# stepper-schematic.net
KiCad netlist of a schematic drawn in Altium Designer
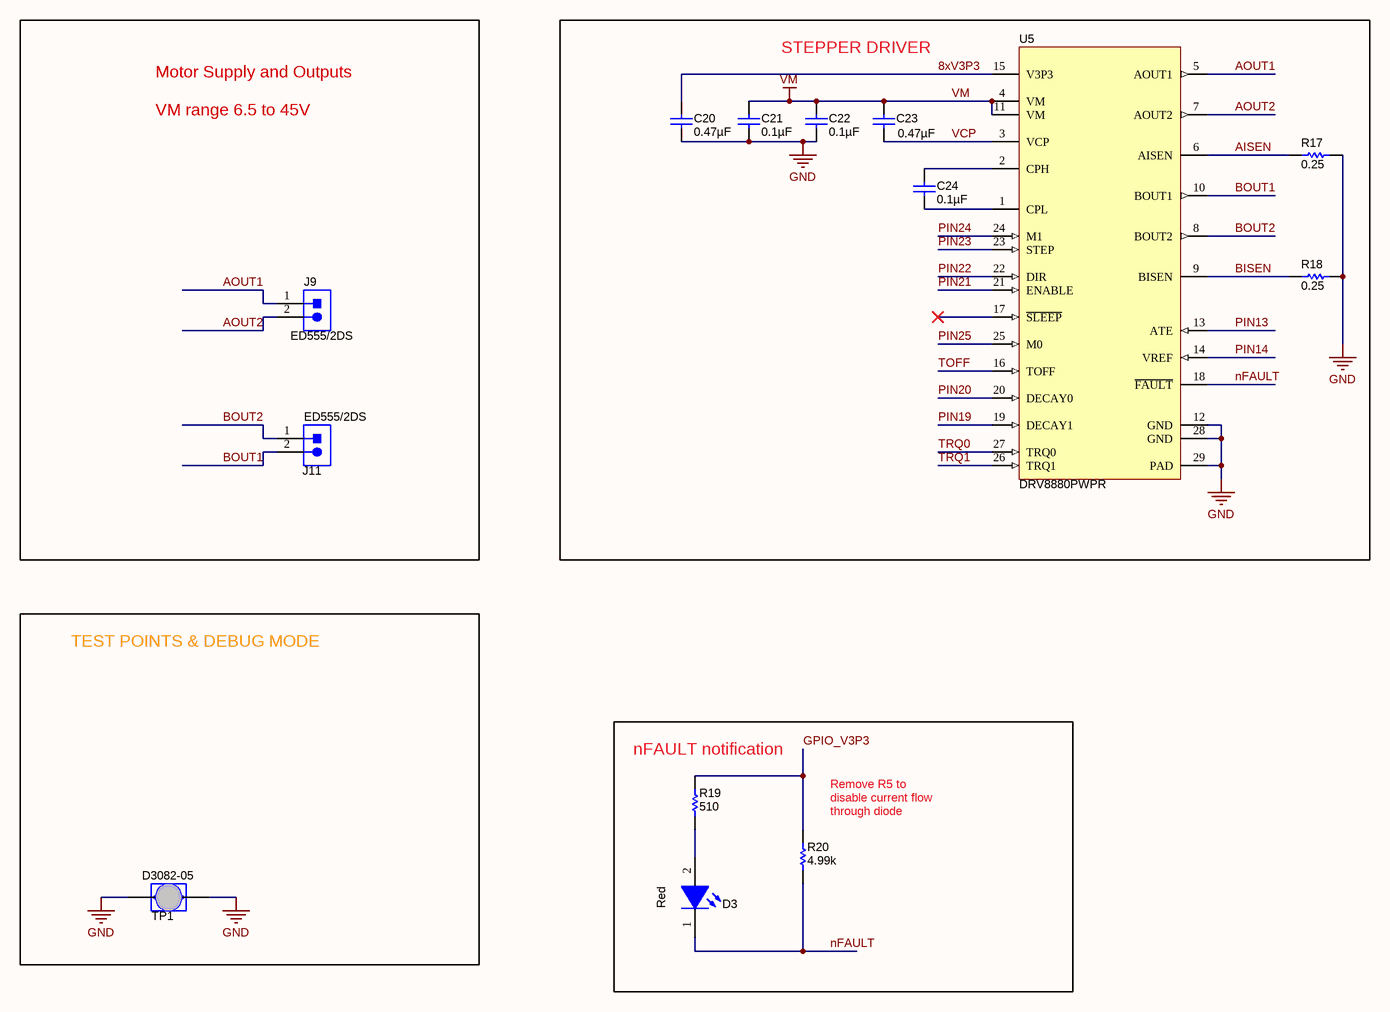
[diagram p0: stepper-schematic.SchDoc]

(export (version "E")
  (design (tool "Eeschema 10.0.6"))
  (components
    (comp (ref "C20")
      (value "C0603C474K9RACTU")
      (footprint "0603L")
      (description "CAP, CERM, 0.47 µF, 6.3 V, +/- 10%, X7R, 0603")
      (fields
        (field (name "MANUFACTURER") "Kemet")
        (field (name "VALUEDISPLAYED") "0.47µF")
        (field (name "PUBLISHER") "Texas Instruments")
      )
      (libsource (lib "drvs-motor") (part "C0603C474K9RACTU"))
    )
    (comp (ref "C21")
      (value "C0805C104K1RACTU")
      (footprint "0805L")
      (description "CAP, CERM, 0.1 µF, 100 V, +/- 10%, X7R, 0805")
      (fields
        (field (name "MANUFACTURER") "Kemet")
        (field (name "VALUEDISPLAYED") "0.1µF")
        (field (name "PUBLISHER") "Texas Instruments")
      )
      (libsource (lib "drvs-motor") (part "C0805C104K1RACTU"))
    )
    (comp (ref "C22")
      (value "C0805C104K1RACTU")
      (footprint "0805L")
      (description "CAP, CERM, 0.1 µF, 100 V, +/- 10%, X7R, 0805")
      (fields
        (field (name "MANUFACTURER") "Kemet")
        (field (name "VALUEDISPLAYED") "0.1µF")
        (field (name "PUBLISHER") "Texas Instruments")
      )
      (libsource (lib "drvs-motor") (part "C0805C104K1RACTU"))
    )
    (comp (ref "C23")
      (value "C2012X7R1E474K")
      (footprint "0805L")
      (description "CAP, CERM, 0.47 µF, 25 V, +/- 10%, X7R, 0805")
      (fields
        (field (name "MANUFACTURER") "TDK")
        (field (name "VALUEDISPLAYED") "0.47µF")
        (field (name "PUBLISHER") "Texas Instruments")
      )
      (libsource (lib "drvs-motor") (part "C2012X7R1E474K"))
    )
    (comp (ref "C24")
      (value "C0805C104K1RACTU")
      (footprint "0805L")
      (description "CAP, CERM, 0.1 µF, 100 V, +/- 10%, X7R, 0805")
      (fields
        (field (name "MANUFACTURER") "Kemet")
        (field (name "VALUEDISPLAYED") "0.1µF")
        (field (name "PUBLISHER") "Texas Instruments")
      )
      (libsource (lib "drvs-motor") (part "C0805C104K1RACTU"))
    )
    (comp (ref "D3")
      (value "Red")
      (footprint "WL-SMCW_RED")
      (description "LED, Red, SMD")
      (fields
        (field (name "MANUFACTURER") "Wurth Elektronik")
        (field (name "PARTNUMBER") "150060RS75000")
        (field (name "PUBLISHER") "Texas Instruments")
      )
      (libsource (lib "drvs-motor") (part "CMP-0002947-2"))
    )
    (comp (ref "J9")
      (value "ED555/2DS")
      (footprint "TERM_BLK_ED555-2DS")
      (description "Terminal Block, 6A, 3.5mm Pitch, 2-Pos, TH")
      (fields
        (field (name "MANUFACTURER") "On-Shore Technology")
        (field (name "SYMBOLCREATOR") "a0412235")
        (field (name "PUBLISHER") "Texas Instruments")
      )
      (libsource (lib "drvs-motor") (part "ED555/2DS"))
    )
    (comp (ref "J11")
      (value "ED555/2DS")
      (footprint "TERM_BLK_ED555-2DS")
      (description "Terminal Block, 6A, 3.5mm Pitch, 2-Pos, TH")
      (fields
        (field (name "MANUFACTURER") "On-Shore Technology")
        (field (name "SYMBOLCREATOR") "a0412235")
        (field (name "PUBLISHER") "Texas Instruments")
      )
      (libsource (lib "drvs-motor") (part "ED555/2DS"))
    )
    (comp (ref "R17")
      (value "0.25")
      (footprint "2010L")
      (description "RES, 0.25, 1%, 1 W, 2010")
      (fields
        (field (name "PARTNUMBER") "CSRN2010FKR250")
        (field (name "MANUFACTURER") "Stackpole Electronics Inc")
        (field (name "PUBLISHER") "Texas Instruments")
      )
      (libsource (lib "drvs-motor") (part "CSRN2010FKR250"))
    )
    (comp (ref "R18")
      (value "0.25")
      (footprint "2010L")
      (description "RES, 0.25, 1%, 1 W, 2010")
      (fields
        (field (name "PARTNUMBER") "CSRN2010FKR250")
        (field (name "MANUFACTURER") "Stackpole Electronics Inc")
        (field (name "PUBLISHER") "Texas Instruments")
      )
      (libsource (lib "drvs-motor") (part "CSRN2010FKR250"))
    )
    (comp (ref "R19")
      (value "510")
      (footprint "0402L")
      (description "RES, 510, 5%, 0.063 W, 0402")
      (fields
        (field (name "PARTNUMBER") "CRCW0402510RJNED")
        (field (name "MANUFACTURER") "Vishay-Dale")
        (field (name "PUBLISHER") "Texas Instruments")
      )
      (libsource (lib "drvs-motor") (part "CRCW0402510RJNED"))
    )
    (comp (ref "R20")
      (value "4.99k")
      (footprint "0402L")
      (description "RES, 4.99 k, 1%, 0.063 W, 0402")
      (fields
        (field (name "PARTNUMBER") "CRCW04024K99FKED")
        (field (name "MANUFACTURER") "Vishay-Dale")
        (field (name "PUBLISHER") "Texas Instruments")
      )
      (libsource (lib "drvs-motor") (part "CRCW04024K99FKED"))
    )
    (comp (ref "TP1")
      (value "D3082-05")
      (footprint "Harwin_D3082-05")
      (description "1mm Uninsulated Shorting Plug, 10.16mm spacing, TH")
      (fields
        (field (name "MANUFACTURER") "Harwin")
        (field (name "SYMBOLCREATOR") "a0799628")
        (field (name "PUBLISHER") "Texas Instruments")
      )
      (libsource (lib "drvs-motor") (part "D3082-05"))
    )
    (comp (ref "U5")
      (value "DRV8880PWPR")
      (footprint "PWP0028C_N")
      (description "2-A 45-V 1/16-μstep Stepper Motor Driver With AutoTune, PWP0028C")
      (fields
        (field (name "ALTERNATE PARTNUMBER") "DRV8880PWP")
        (field (name "MANUFACTURER") "Texas Instruments")
        (field (name "SYMBOLCREATOR") "Altium")
        (field (name "PUBLISHER") "Texas Instruments")
      )
      (libsource (lib "drvs-motor") (part "DRV8880PWPR"))
    )
  )
  (nets
    (net (code "1") (name "/8xV3P3") (class "Default")
      (node (ref "C20") (pin "1") (pinfunction "1_1") (pintype "passive"))
      (node (ref "U5") (pin "15") (pinfunction "V3P3_15") (pintype "power_in"))
    )
    (net (code "2") (name "/AISEN") (class "Default")
      (node (ref "R17") (pin "2") (pinfunction "2_2") (pintype "passive"))
      (node (ref "U5") (pin "6") (pinfunction "AISEN_6") (pintype "passive"))
    )
    (net (code "3") (name "/AOUT1") (class "Default")
      (node (ref "J9") (pin "1") (pinfunction "1_1") (pintype "passive"))
      (node (ref "U5") (pin "5") (pinfunction "AOUT1_5") (pintype "output"))
    )
    (net (code "4") (name "/AOUT2") (class "Default")
      (node (ref "J9") (pin "2") (pinfunction "2_2") (pintype "passive"))
      (node (ref "U5") (pin "7") (pinfunction "AOUT2_7") (pintype "output"))
    )
    (net (code "5") (name "/BISEN") (class "Default")
      (node (ref "R18") (pin "2") (pinfunction "2_2") (pintype "passive"))
      (node (ref "U5") (pin "9") (pinfunction "BISEN_9") (pintype "passive"))
    )
    (net (code "6") (name "/BOUT1") (class "Default")
      (node (ref "J11") (pin "2") (pinfunction "2_2") (pintype "passive"))
      (node (ref "U5") (pin "10") (pinfunction "BOUT1_10") (pintype "output"))
    )
    (net (code "7") (name "/BOUT2") (class "Default")
      (node (ref "J11") (pin "1") (pinfunction "1_1") (pintype "passive"))
      (node (ref "U5") (pin "8") (pinfunction "BOUT2_8") (pintype "output"))
    )
    (net (code "8") (name "/GPIO_V3P3") (class "Default")
      (node (ref "R19") (pin "2") (pinfunction "2_2") (pintype "passive"))
      (node (ref "R20") (pin "2") (pinfunction "2_2") (pintype "passive"))
    )
    (net (code "9") (name "/PIN13") (class "Default")
      (node (ref "U5") (pin "13") (pinfunction "ATE_13") (pintype "input"))
    )
    (net (code "10") (name "/PIN14") (class "Default")
      (node (ref "U5") (pin "14") (pinfunction "VREF_14") (pintype "input"))
    )
    (net (code "11") (name "/PIN19") (class "Default")
      (node (ref "U5") (pin "19") (pinfunction "DECAY1_19") (pintype "input"))
    )
    (net (code "12") (name "/PIN20") (class "Default")
      (node (ref "U5") (pin "20") (pinfunction "DECAY0_20") (pintype "input"))
    )
    (net (code "13") (name "/PIN21") (class "Default")
      (node (ref "U5") (pin "21") (pinfunction "ENABLE_21") (pintype "input"))
    )
    (net (code "14") (name "/PIN22") (class "Default")
      (node (ref "U5") (pin "22") (pinfunction "DIR_22") (pintype "input"))
    )
    (net (code "15") (name "/PIN23") (class "Default")
      (node (ref "U5") (pin "23") (pinfunction "STEP_23") (pintype "input"))
    )
    (net (code "16") (name "/PIN24") (class "Default")
      (node (ref "U5") (pin "24") (pinfunction "M1_24") (pintype "input"))
    )
    (net (code "17") (name "/PIN25") (class "Default")
      (node (ref "U5") (pin "25") (pinfunction "M0_25") (pintype "input"))
    )
    (net (code "18") (name "/TOFF") (class "Default")
      (node (ref "U5") (pin "16") (pinfunction "TOFF_16") (pintype "input"))
    )
    (net (code "19") (name "/TRQ0") (class "Default")
      (node (ref "U5") (pin "27") (pinfunction "TRQ0_27") (pintype "input"))
    )
    (net (code "20") (name "/TRQ1") (class "Default")
      (node (ref "U5") (pin "26") (pinfunction "TRQ1_26") (pintype "input"))
    )
    (net (code "21") (name "/VCP") (class "Default")
      (node (ref "C23") (pin "1") (pinfunction "1_1") (pintype "passive"))
      (node (ref "U5") (pin "3") (pinfunction "VCP_3") (pintype "passive"))
    )
    (net (code "22") (name "/nFAULT") (class "Default")
      (node (ref "D3") (pin "1") (pinfunction "K_1") (pintype "passive"))
      (node (ref "R20") (pin "1") (pinfunction "1_1") (pintype "passive"))
      (node (ref "U5") (pin "18") (pinfunction "FAULT_18") (pintype "open_collector"))
    )
    (net (code "23") (name "GND") (class "Default")
      (node (ref "C20") (pin "2") (pinfunction "2_2") (pintype "passive"))
      (node (ref "C21") (pin "1") (pinfunction "1_1") (pintype "passive"))
      (node (ref "C22") (pin "1") (pinfunction "1_1") (pintype "passive"))
      (node (ref "R17") (pin "1") (pinfunction "1_1") (pintype "passive"))
      (node (ref "R18") (pin "1") (pinfunction "1_1") (pintype "passive"))
      (node (ref "TP1") (pin "1") (pinfunction "1_1") (pintype "passive"))
      (node (ref "TP1") (pin "2") (pinfunction "2_2") (pintype "passive"))
      (node (ref "U5") (pin "12") (pinfunction "GND_12") (pintype "power_in"))
      (node (ref "U5") (pin "28") (pinfunction "GND_28") (pintype "power_in"))
      (node (ref "U5") (pin "29") (pinfunction "PAD_29") (pintype "power_in"))
    )
    (net (code "24") (name "Net-(D3-A)") (class "Default")
      (node (ref "D3") (pin "2") (pinfunction "A_2") (pintype "passive"))
      (node (ref "R19") (pin "1") (pinfunction "1_1") (pintype "passive"))
    )
    (net (code "25") (name "Net-(U5-CPH)") (class "Default")
      (node (ref "C24") (pin "2") (pinfunction "2_2") (pintype "passive"))
      (node (ref "U5") (pin "2") (pinfunction "CPH_2") (pintype "passive"))
    )
    (net (code "26") (name "Net-(U5-CPL)") (class "Default")
      (node (ref "C24") (pin "1") (pinfunction "1_1") (pintype "passive"))
      (node (ref "U5") (pin "1") (pinfunction "CPL_1") (pintype "passive"))
    )
    (net (code "27") (name "VM") (class "Default")
      (node (ref "C21") (pin "2") (pinfunction "2_2") (pintype "passive"))
      (node (ref "C22") (pin "2") (pinfunction "2_2") (pintype "passive"))
      (node (ref "C23") (pin "2") (pinfunction "2_2") (pintype "passive"))
      (node (ref "U5") (pin "11") (pinfunction "VM_11") (pintype "power_in"))
      (node (ref "U5") (pin "4") (pinfunction "VM_4") (pintype "power_in"))
    )
    (net (code "28") (name "unconnected-(U5-SLEEP-Pad17)") (class "Default")
      (node (ref "U5") (pin "17") (pinfunction "SLEEP_17") (pintype "input+no_connect"))
    )
  )
)
